# MegaAMP_Mk2.net
KiCad netlist of a schematic drawn in EAGLE
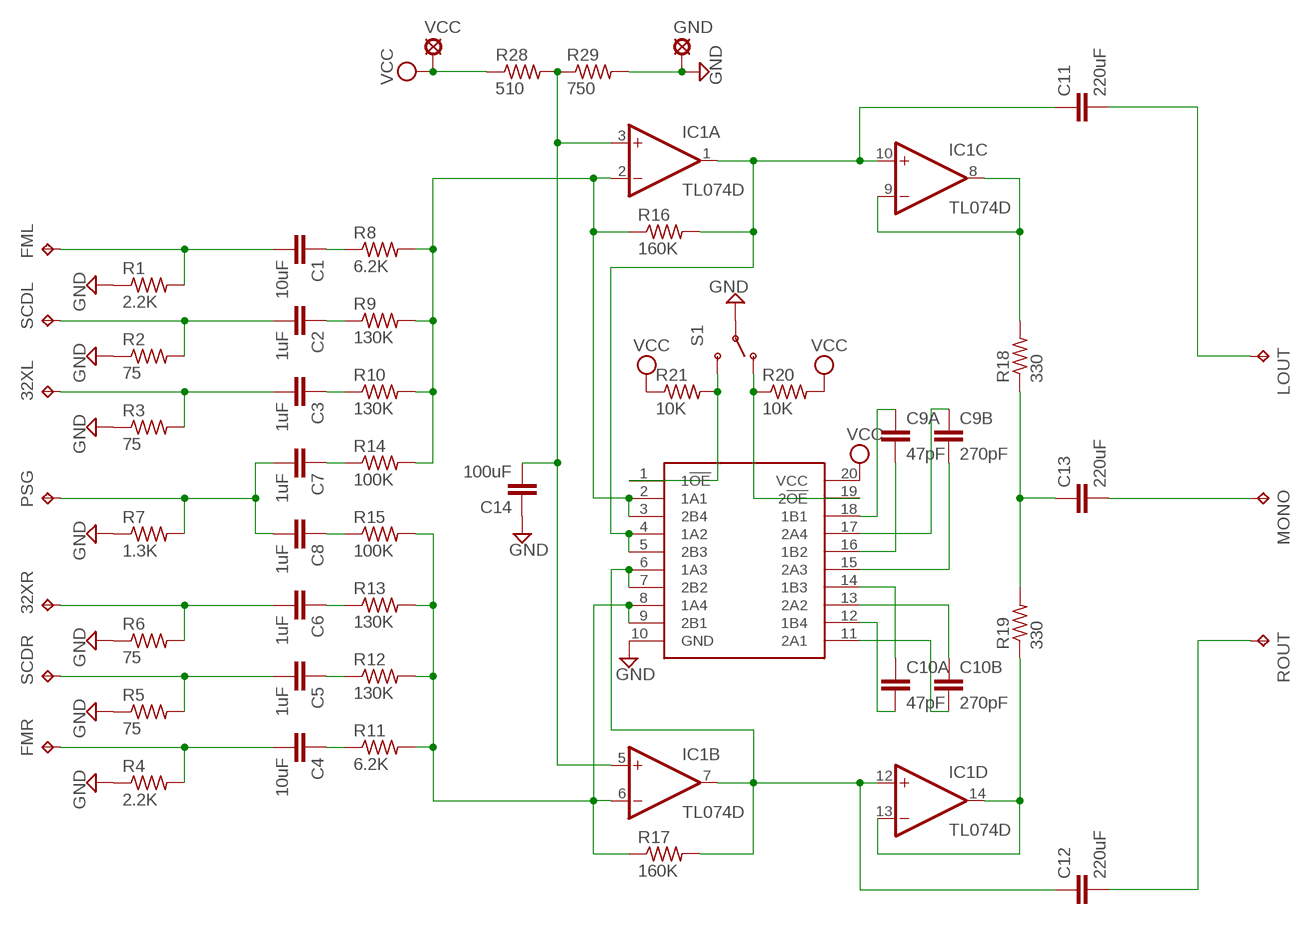
[diagram p0: schematic, sheet 1]

(export (version "E")
  (design (tool "Eeschema 10.0.6"))
  (components
    (comp (ref "32XL")
      (value "TPTP20R")
      (footprint "eagle-import:TP20R")
      (libsource (lib "eagle-import") (part "TPTP20R"))
    )
    (comp (ref "32XR")
      (value "TPTP20R")
      (footprint "eagle-import:TP20R")
      (libsource (lib "eagle-import") (part "TPTP20R"))
    )
    (comp (ref "C1")
      (value "10uF")
      (footprint "eagle-import:C0805")
      (libsource (lib "eagle-import") (part "C-EUC0805"))
    )
    (comp (ref "C2")
      (value "1uF")
      (footprint "eagle-import:C0805")
      (libsource (lib "eagle-import") (part "C-EUC0805"))
    )
    (comp (ref "C3")
      (value "1uF")
      (footprint "eagle-import:C0805")
      (libsource (lib "eagle-import") (part "C-EUC0805"))
    )
    (comp (ref "C4")
      (value "10uF")
      (footprint "eagle-import:C0805")
      (libsource (lib "eagle-import") (part "C-EUC0805"))
    )
    (comp (ref "C5")
      (value "1uF")
      (footprint "eagle-import:C0805")
      (libsource (lib "eagle-import") (part "C-EUC0805"))
    )
    (comp (ref "C6")
      (value "1uF")
      (footprint "eagle-import:C0805")
      (libsource (lib "eagle-import") (part "C-EUC0805"))
    )
    (comp (ref "C7")
      (value "1uF")
      (footprint "eagle-import:C0805")
      (libsource (lib "eagle-import") (part "C-EUC0805"))
    )
    (comp (ref "C8")
      (value "1uF")
      (footprint "eagle-import:C0805")
      (libsource (lib "eagle-import") (part "C-EUC0805"))
    )
    (comp (ref "C9A")
      (value "47pF")
      (footprint "eagle-import:C0805")
      (libsource (lib "eagle-import") (part "C-EUC0805"))
    )
    (comp (ref "C9B")
      (value "270pF")
      (footprint "eagle-import:C0805")
      (libsource (lib "eagle-import") (part "C-EUC0805"))
    )
    (comp (ref "C10A")
      (value "47pF")
      (footprint "eagle-import:C0805")
      (libsource (lib "eagle-import") (part "C-EUC0805"))
    )
    (comp (ref "C10B")
      (value "270pF")
      (footprint "eagle-import:C0805")
      (libsource (lib "eagle-import") (part "C-EUC0805"))
    )
    (comp (ref "C11")
      (value "220uF")
      (footprint "eagle-import:C1210")
      (libsource (lib "eagle-import") (part "resistor_C-EUC1210"))
    )
    (comp (ref "C12")
      (value "220uF")
      (footprint "eagle-import:C1210")
      (libsource (lib "eagle-import") (part "resistor_C-EUC1210"))
    )
    (comp (ref "C13")
      (value "220uF")
      (footprint "eagle-import:C1210")
      (libsource (lib "eagle-import") (part "resistor_C-EUC1210"))
    )
    (comp (ref "C14")
      (value "100uF")
      (footprint "eagle-import:C1206")
      (libsource (lib "eagle-import") (part "resistor_C-EUC1206"))
    )
    (comp (ref "FML")
      (value "TPTP20R")
      (footprint "eagle-import:TP20R")
      (libsource (lib "eagle-import") (part "TPTP20R"))
    )
    (comp (ref "FMR")
      (value "TPTP20R")
      (footprint "eagle-import:TP20R")
      (libsource (lib "eagle-import") (part "TPTP20R"))
    )
    (comp (ref "GND")
      (value "LSP13")
      (footprint "eagle-import:LSP13")
      (libsource (lib "eagle-import") (part "LSP13"))
    )
    (comp (ref "IC1")
      (value "TL074D")
      (footprint "eagle-import:SO14")
      (libsource (lib "eagle-import") (part "TL074D"))
    )
    (comp (ref "LOUT")
      (value "TPTP20R")
      (footprint "eagle-import:TP20R")
      (libsource (lib "eagle-import") (part "TPTP20R"))
    )
    (comp (ref "MONO")
      (value "TPTP20R")
      (footprint "eagle-import:TP20R")
      (libsource (lib "eagle-import") (part "TPTP20R"))
    )
    (comp (ref "PSG")
      (value "TPTP20R")
      (footprint "eagle-import:TP20R")
      (libsource (lib "eagle-import") (part "TPTP20R"))
    )
    (comp (ref "R1")
      (value "2.2K")
      (footprint "eagle-import:R0805")
      (libsource (lib "eagle-import") (part "R-US_R0805"))
    )
    (comp (ref "R2")
      (value "75")
      (footprint "eagle-import:R0805")
      (libsource (lib "eagle-import") (part "R-US_R0805"))
    )
    (comp (ref "R3")
      (value "75")
      (footprint "eagle-import:R0805")
      (libsource (lib "eagle-import") (part "R-US_R0805"))
    )
    (comp (ref "R4")
      (value "2.2K")
      (footprint "eagle-import:R0805")
      (libsource (lib "eagle-import") (part "R-US_R0805"))
    )
    (comp (ref "R5")
      (value "75")
      (footprint "eagle-import:R0805")
      (libsource (lib "eagle-import") (part "R-US_R0805"))
    )
    (comp (ref "R6")
      (value "75")
      (footprint "eagle-import:R0805")
      (libsource (lib "eagle-import") (part "R-US_R0805"))
    )
    (comp (ref "R7")
      (value "1.3K")
      (footprint "eagle-import:R0805")
      (libsource (lib "eagle-import") (part "R-US_R0805"))
    )
    (comp (ref "R8")
      (value "6.2K")
      (footprint "eagle-import:R0805")
      (libsource (lib "eagle-import") (part "R-US_R0805"))
    )
    (comp (ref "R9")
      (value "130K")
      (footprint "eagle-import:R0805")
      (libsource (lib "eagle-import") (part "R-US_R0805"))
    )
    (comp (ref "R10")
      (value "130K")
      (footprint "eagle-import:R0805")
      (libsource (lib "eagle-import") (part "R-US_R0805"))
    )
    (comp (ref "R11")
      (value "6.2K")
      (footprint "eagle-import:R0805")
      (libsource (lib "eagle-import") (part "R-US_R0805"))
    )
    (comp (ref "R12")
      (value "130K")
      (footprint "eagle-import:R0805")
      (libsource (lib "eagle-import") (part "R-US_R0805"))
    )
    (comp (ref "R13")
      (value "130K")
      (footprint "eagle-import:R0805")
      (libsource (lib "eagle-import") (part "R-US_R0805"))
    )
    (comp (ref "R14")
      (value "100K")
      (footprint "eagle-import:R0805")
      (libsource (lib "eagle-import") (part "R-US_R0805"))
    )
    (comp (ref "R15")
      (value "100K")
      (footprint "eagle-import:R0805")
      (libsource (lib "eagle-import") (part "R-US_R0805"))
    )
    (comp (ref "R16")
      (value "160K")
      (footprint "eagle-import:R0805")
      (libsource (lib "eagle-import") (part "R-US_R0805"))
    )
    (comp (ref "R17")
      (value "160K")
      (footprint "eagle-import:R0805")
      (libsource (lib "eagle-import") (part "R-US_R0805"))
    )
    (comp (ref "R18")
      (value "330")
      (footprint "eagle-import:R0805")
      (libsource (lib "eagle-import") (part "R-US_R0805"))
    )
    (comp (ref "R19")
      (value "330")
      (footprint "eagle-import:R0805")
      (libsource (lib "eagle-import") (part "R-US_R0805"))
    )
    (comp (ref "R20")
      (value "10K")
      (footprint "eagle-import:R0805")
      (libsource (lib "eagle-import") (part "R-US_R0805"))
    )
    (comp (ref "R21")
      (value "10K")
      (footprint "eagle-import:R0805")
      (libsource (lib "eagle-import") (part "R-US_R0805"))
    )
    (comp (ref "R28")
      (value "510")
      (footprint "eagle-import:R0805")
      (libsource (lib "eagle-import") (part "R-US_R0805"))
    )
    (comp (ref "R29")
      (value "750")
      (footprint "eagle-import:R0805")
      (libsource (lib "eagle-import") (part "R-US_R0805"))
    )
    (comp (ref "ROUT")
      (value "TPTP20R")
      (footprint "eagle-import:TP20R")
      (libsource (lib "eagle-import") (part "TPTP20R"))
    )
    (comp (ref "S1")
      (value "SWITCH-SPDTPTH")
      (footprint "eagle-import:SWITCH-SPDT")
      (libsource (lib "eagle-import") (part "SWITCH-SPDTPTH"))
    )
    (comp (ref "SCDL")
      (value "TPTP20R")
      (footprint "eagle-import:TP20R")
      (libsource (lib "eagle-import") (part "TPTP20R"))
    )
    (comp (ref "SCDR")
      (value "TPTP20R")
      (footprint "eagle-import:TP20R")
      (libsource (lib "eagle-import") (part "TPTP20R"))
    )
    (comp (ref "U$1")
      (value "DBQ(R-PDS0-G20)")
      (footprint "eagle-import:DBQ(R-PDSO-G20)")
      (libsource (lib "eagle-import") (part "DBQ(R-PDS0-G20)"))
    )
    (comp (ref "VCC")
      (value "LSP13")
      (footprint "eagle-import:LSP13")
      (libsource (lib "eagle-import") (part "LSP13"))
    )
  )
  (nets
    (net (code "1") (name "GND") (class "Default")
      (node (ref "C14") (pin "1") (pinfunction "1_1") (pintype "passive"))
      (node (ref "GND") (pin "MP") (pinfunction "MP_MP") (pintype "passive"))
      (node (ref "R1") (pin "1") (pinfunction "1_1") (pintype "passive"))
      (node (ref "R2") (pin "1") (pinfunction "1_1") (pintype "passive"))
      (node (ref "R29") (pin "2") (pinfunction "2_2") (pintype "passive"))
      (node (ref "R3") (pin "1") (pinfunction "1_1") (pintype "passive"))
      (node (ref "R4") (pin "1") (pinfunction "1_1") (pintype "passive"))
      (node (ref "R5") (pin "1") (pinfunction "1_1") (pintype "passive"))
      (node (ref "R6") (pin "1") (pinfunction "1_1") (pintype "passive"))
      (node (ref "R7") (pin "1") (pinfunction "1_1") (pintype "passive"))
      (node (ref "S1") (pin "2") (pinfunction "P_2") (pintype "passive"))
      (node (ref "U$1") (pin "10") (pinfunction "GND_10") (pintype "power_in"))
    )
    (net (code "2") (name "Net-(32XL-PadTP)") (class "Default")
      (node (ref "32XL") (pin "TP") (pinfunction "TP_TP") (pintype "input"))
      (node (ref "C3") (pin "2") (pinfunction "2_2") (pintype "passive"))
      (node (ref "R3") (pin "2") (pinfunction "2_2") (pintype "passive"))
    )
    (net (code "3") (name "Net-(32XR-PadTP)") (class "Default")
      (node (ref "32XR") (pin "TP") (pinfunction "TP_TP") (pintype "input"))
      (node (ref "C6") (pin "2") (pinfunction "2_2") (pintype "passive"))
      (node (ref "R6") (pin "2") (pinfunction "2_2") (pintype "passive"))
    )
    (net (code "4") (name "Net-(C1-Pad1)") (class "Default")
      (node (ref "C1") (pin "1") (pinfunction "1_1") (pintype "passive"))
      (node (ref "R8") (pin "1") (pinfunction "1_1") (pintype "passive"))
    )
    (net (code "5") (name "Net-(C1-Pad2)") (class "Default")
      (node (ref "C1") (pin "2") (pinfunction "2_2") (pintype "passive"))
      (node (ref "FML") (pin "TP") (pinfunction "TP_TP") (pintype "input"))
      (node (ref "R1") (pin "2") (pinfunction "2_2") (pintype "passive"))
    )
    (net (code "6") (name "Net-(C2-Pad1)") (class "Default")
      (node (ref "C2") (pin "1") (pinfunction "1_1") (pintype "passive"))
      (node (ref "R9") (pin "1") (pinfunction "1_1") (pintype "passive"))
    )
    (net (code "7") (name "Net-(C2-Pad2)") (class "Default")
      (node (ref "C2") (pin "2") (pinfunction "2_2") (pintype "passive"))
      (node (ref "R2") (pin "2") (pinfunction "2_2") (pintype "passive"))
      (node (ref "SCDL") (pin "TP") (pinfunction "TP_TP") (pintype "input"))
    )
    (net (code "8") (name "Net-(C3-Pad1)") (class "Default")
      (node (ref "C3") (pin "1") (pinfunction "1_1") (pintype "passive"))
      (node (ref "R10") (pin "1") (pinfunction "1_1") (pintype "passive"))
    )
    (net (code "9") (name "Net-(C4-Pad1)") (class "Default")
      (node (ref "C4") (pin "1") (pinfunction "1_1") (pintype "passive"))
      (node (ref "R11") (pin "1") (pinfunction "1_1") (pintype "passive"))
    )
    (net (code "10") (name "Net-(C4-Pad2)") (class "Default")
      (node (ref "C4") (pin "2") (pinfunction "2_2") (pintype "passive"))
      (node (ref "FMR") (pin "TP") (pinfunction "TP_TP") (pintype "input"))
      (node (ref "R4") (pin "2") (pinfunction "2_2") (pintype "passive"))
    )
    (net (code "11") (name "Net-(C5-Pad1)") (class "Default")
      (node (ref "C5") (pin "1") (pinfunction "1_1") (pintype "passive"))
      (node (ref "R12") (pin "1") (pinfunction "1_1") (pintype "passive"))
    )
    (net (code "12") (name "Net-(C5-Pad2)") (class "Default")
      (node (ref "C5") (pin "2") (pinfunction "2_2") (pintype "passive"))
      (node (ref "R5") (pin "2") (pinfunction "2_2") (pintype "passive"))
      (node (ref "SCDR") (pin "TP") (pinfunction "TP_TP") (pintype "input"))
    )
    (net (code "13") (name "Net-(C6-Pad1)") (class "Default")
      (node (ref "C6") (pin "1") (pinfunction "1_1") (pintype "passive"))
      (node (ref "R13") (pin "1") (pinfunction "1_1") (pintype "passive"))
    )
    (net (code "14") (name "Net-(C7-Pad1)") (class "Default")
      (node (ref "C7") (pin "1") (pinfunction "1_1") (pintype "passive"))
      (node (ref "R14") (pin "1") (pinfunction "1_1") (pintype "passive"))
    )
    (net (code "15") (name "Net-(C7-Pad2)") (class "Default")
      (node (ref "C7") (pin "2") (pinfunction "2_2") (pintype "passive"))
      (node (ref "C8") (pin "2") (pinfunction "2_2") (pintype "passive"))
      (node (ref "PSG") (pin "TP") (pinfunction "TP_TP") (pintype "input"))
      (node (ref "R7") (pin "2") (pinfunction "2_2") (pintype "passive"))
    )
    (net (code "16") (name "Net-(C8-Pad1)") (class "Default")
      (node (ref "C8") (pin "1") (pinfunction "1_1") (pintype "passive"))
      (node (ref "R15") (pin "1") (pinfunction "1_1") (pintype "passive"))
    )
    (net (code "17") (name "Net-(C11-Pad2)") (class "Default")
      (node (ref "C11") (pin "2") (pinfunction "2_2") (pintype "passive"))
      (node (ref "LOUT") (pin "TP") (pinfunction "TP_TP") (pintype "input"))
    )
    (net (code "18") (name "Net-(C12-Pad2)") (class "Default")
      (node (ref "C12") (pin "2") (pinfunction "2_2") (pintype "passive"))
      (node (ref "ROUT") (pin "TP") (pinfunction "TP_TP") (pintype "input"))
    )
    (net (code "19") (name "Net-(C13-Pad1)") (class "Default")
      (node (ref "C13") (pin "1") (pinfunction "1_1") (pintype "passive"))
      (node (ref "R18") (pin "1") (pinfunction "1_1") (pintype "passive"))
      (node (ref "R19") (pin "2") (pinfunction "2_2") (pintype "passive"))
    )
    (net (code "20") (name "Net-(C13-Pad2)") (class "Default")
      (node (ref "C13") (pin "2") (pinfunction "2_2") (pintype "passive"))
      (node (ref "MONO") (pin "TP") (pinfunction "TP_TP") (pintype "input"))
    )
    (net (code "21") (name "Net-(IC1A-+IN)") (class "Default")
      (node (ref "C14") (pin "2") (pinfunction "2_2") (pintype "passive"))
      (node (ref "IC1") (pin "3") (pinfunction "+IN_3") (pintype "input"))
      (node (ref "IC1") (pin "5") (pinfunction "+IN_5") (pintype "input"))
      (node (ref "R28") (pin "2") (pinfunction "2_2") (pintype "passive"))
      (node (ref "R29") (pin "1") (pinfunction "1_1") (pintype "passive"))
    )
    (net (code "22") (name "Net-(IC1A--IN)") (class "Default")
      (node (ref "IC1") (pin "2") (pinfunction "-IN_2") (pintype "input"))
      (node (ref "R10") (pin "2") (pinfunction "2_2") (pintype "passive"))
      (node (ref "R14") (pin "2") (pinfunction "2_2") (pintype "passive"))
      (node (ref "R16") (pin "1") (pinfunction "1_1") (pintype "passive"))
      (node (ref "R8") (pin "2") (pinfunction "2_2") (pintype "passive"))
      (node (ref "R9") (pin "2") (pinfunction "2_2") (pintype "passive"))
      (node (ref "U$1") (pin "2") (pinfunction "1A1_2") (pintype "bidirectional"))
      (node (ref "U$1") (pin "3") (pinfunction "2B4_3") (pintype "bidirectional"))
    )
    (net (code "23") (name "Net-(IC1A-OUT)") (class "Default")
      (node (ref "C11") (pin "1") (pinfunction "1_1") (pintype "passive"))
      (node (ref "IC1") (pin "1") (pinfunction "OUT_1") (pintype "output"))
      (node (ref "IC1") (pin "10") (pinfunction "+IN_10") (pintype "input"))
      (node (ref "R16") (pin "2") (pinfunction "2_2") (pintype "passive"))
      (node (ref "U$1") (pin "4") (pinfunction "1A2_4") (pintype "bidirectional"))
      (node (ref "U$1") (pin "5") (pinfunction "2B3_5") (pintype "bidirectional"))
    )
    (net (code "24") (name "Net-(IC1B--IN)") (class "Default")
      (node (ref "IC1") (pin "6") (pinfunction "-IN_6") (pintype "input"))
      (node (ref "R11") (pin "2") (pinfunction "2_2") (pintype "passive"))
      (node (ref "R12") (pin "2") (pinfunction "2_2") (pintype "passive"))
      (node (ref "R13") (pin "2") (pinfunction "2_2") (pintype "passive"))
      (node (ref "R15") (pin "2") (pinfunction "2_2") (pintype "passive"))
      (node (ref "R17") (pin "1") (pinfunction "1_1") (pintype "passive"))
      (node (ref "U$1") (pin "8") (pinfunction "1A4_8") (pintype "bidirectional"))
      (node (ref "U$1") (pin "9") (pinfunction "2B1_9") (pintype "bidirectional"))
    )
    (net (code "25") (name "Net-(IC1B-OUT)") (class "Default")
      (node (ref "C12") (pin "1") (pinfunction "1_1") (pintype "passive"))
      (node (ref "IC1") (pin "12") (pinfunction "+IN_12") (pintype "input"))
      (node (ref "IC1") (pin "7") (pinfunction "OUT_7") (pintype "output"))
      (node (ref "R17") (pin "2") (pinfunction "2_2") (pintype "passive"))
      (node (ref "U$1") (pin "6") (pinfunction "1A3_6") (pintype "bidirectional"))
      (node (ref "U$1") (pin "7") (pinfunction "2B2_7") (pintype "bidirectional"))
    )
    (net (code "26") (name "Net-(IC1C--IN)") (class "Default")
      (node (ref "IC1") (pin "8") (pinfunction "OUT_8") (pintype "output"))
      (node (ref "IC1") (pin "9") (pinfunction "-IN_9") (pintype "input"))
      (node (ref "R18") (pin "2") (pinfunction "2_2") (pintype "passive"))
    )
    (net (code "27") (name "Net-(IC1D--IN)") (class "Default")
      (node (ref "IC1") (pin "13") (pinfunction "-IN_13") (pintype "input"))
      (node (ref "IC1") (pin "14") (pinfunction "OUT_14") (pintype "output"))
      (node (ref "R19") (pin "1") (pinfunction "1_1") (pintype "passive"))
    )
    (net (code "28") (name "Net-(S1-O)") (class "Default")
      (node (ref "R20") (pin "1") (pinfunction "1_1") (pintype "passive"))
      (node (ref "S1") (pin "1") (pinfunction "O_1") (pintype "passive"))
      (node (ref "U$1") (pin "19") (pinfunction "2~{OE}_19") (pintype "bidirectional"))
    )
    (net (code "29") (name "Net-(S1-S)") (class "Default")
      (node (ref "R21") (pin "2") (pinfunction "2_2") (pintype "passive"))
      (node (ref "S1") (pin "3") (pinfunction "S_3") (pintype "passive"))
      (node (ref "U$1") (pin "1") (pinfunction "1~{OE}_1") (pintype "bidirectional"))
    )
    (net (code "30") (name "Net-(U$1-1B1)") (class "Default")
      (node (ref "C9A") (pin "1") (pinfunction "1_1") (pintype "passive"))
      (node (ref "U$1") (pin "18") (pinfunction "1B1_18") (pintype "bidirectional"))
    )
    (net (code "31") (name "Net-(U$1-1B2)") (class "Default")
      (node (ref "C9A") (pin "2") (pinfunction "2_2") (pintype "passive"))
      (node (ref "U$1") (pin "16") (pinfunction "1B2_16") (pintype "bidirectional"))
    )
    (net (code "32") (name "Net-(U$1-1B3)") (class "Default")
      (node (ref "C10A") (pin "1") (pinfunction "1_1") (pintype "passive"))
      (node (ref "U$1") (pin "14") (pinfunction "1B3_14") (pintype "bidirectional"))
    )
    (net (code "33") (name "Net-(U$1-1B4)") (class "Default")
      (node (ref "C10A") (pin "2") (pinfunction "2_2") (pintype "passive"))
      (node (ref "U$1") (pin "12") (pinfunction "1B4_12") (pintype "bidirectional"))
    )
    (net (code "34") (name "Net-(U$1-2A1)") (class "Default")
      (node (ref "C10B") (pin "2") (pinfunction "2_2") (pintype "passive"))
      (node (ref "U$1") (pin "11") (pinfunction "2A1_11") (pintype "bidirectional"))
    )
    (net (code "35") (name "Net-(U$1-2A2)") (class "Default")
      (node (ref "C10B") (pin "1") (pinfunction "1_1") (pintype "passive"))
      (node (ref "U$1") (pin "13") (pinfunction "2A2_13") (pintype "bidirectional"))
    )
    (net (code "36") (name "Net-(U$1-2A3)") (class "Default")
      (node (ref "C9B") (pin "2") (pinfunction "2_2") (pintype "passive"))
      (node (ref "U$1") (pin "15") (pinfunction "2A3_15") (pintype "bidirectional"))
    )
    (net (code "37") (name "Net-(U$1-2A4)") (class "Default")
      (node (ref "C9B") (pin "1") (pinfunction "1_1") (pintype "passive"))
      (node (ref "U$1") (pin "17") (pinfunction "2A4_17") (pintype "bidirectional"))
    )
    (net (code "38") (name "VCC") (class "Default")
      (node (ref "R20") (pin "2") (pinfunction "2_2") (pintype "passive"))
      (node (ref "R21") (pin "1") (pinfunction "1_1") (pintype "passive"))
      (node (ref "R28") (pin "1") (pinfunction "1_1") (pintype "passive"))
      (node (ref "U$1") (pin "20") (pinfunction "VCC_20") (pintype "power_in"))
      (node (ref "VCC") (pin "MP") (pinfunction "MP_MP") (pintype "passive"))
    )
  )
)
